# Power.net
KiCad netlist of a schematic drawn in Altium Designer
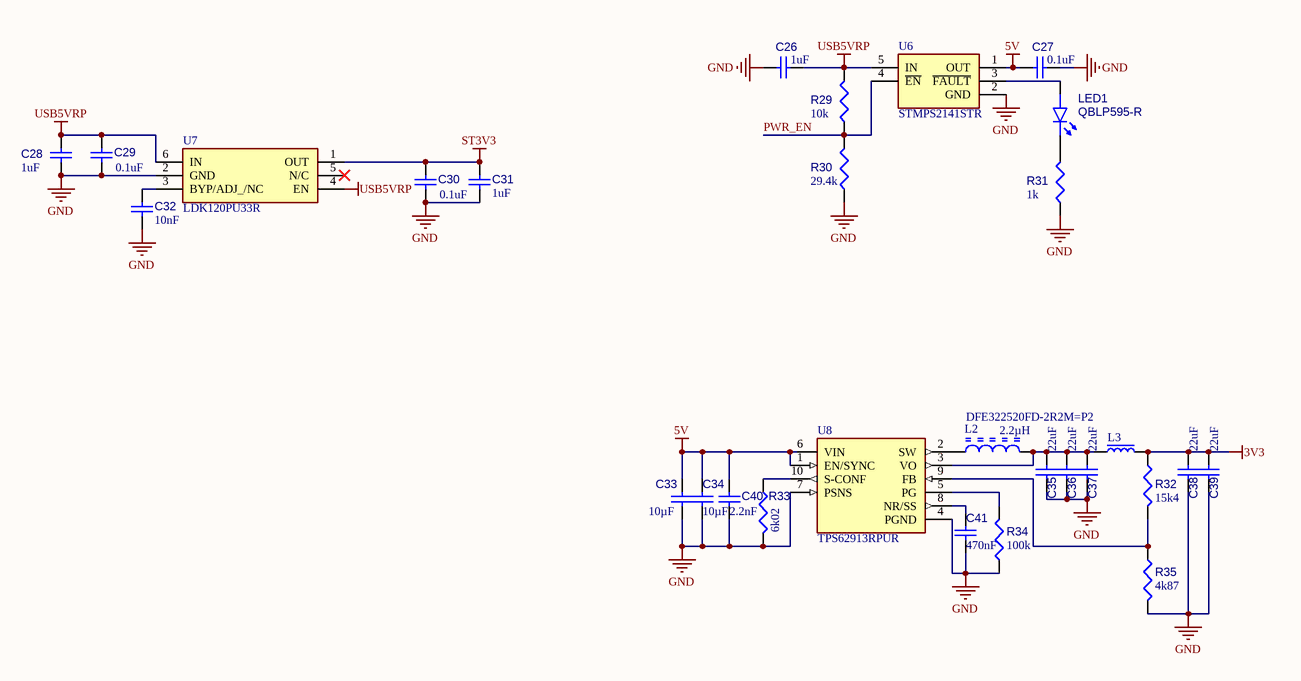
[diagram p0: Power.SchDoc]

(export (version "E")
  (design (tool "Eeschema 10.0.6"))
  (components
    (comp (ref "C26")
      (value "1uF")
      (footprint "CAPC1005X55X25ML05T05")
      (description "Chip Capacitor, 10 pF, +/- 5%, 50 V, 0402 (1005 Metric)")
      (fields (field (name "TOLERANCE") "5%") (field (name "Comment") "Capacitor 10 pF +/- 5% 50 V 0402"))
      (libsource (lib "Fei Han") (part "CAP-NP-2"))
    )
    (comp (ref "C27")
      (value "0.1uF")
      (footprint "CAPC1005X55X25ML05T05")
      (description "Chip Capacitor, 10 pF, +/- 5%, 50 V, 0402 (1005 Metric)")
      (fields (field (name "TOLERANCE") "5%") (field (name "Comment") "Capacitor 10 pF +/- 5% 50 V 0402"))
      (libsource (lib "Fei Han") (part "CAP-NP-2"))
    )
    (comp (ref "C28")
      (value "1uF")
      (footprint "CAPC1005X55X25ML05T05")
      (description "Chip Capacitor, 10 pF, +/- 5%, 50 V, 0402 (1005 Metric)")
      (fields (field (name "TOLERANCE") "5%") (field (name "Comment") "Capacitor 10 pF +/- 5% 50 V 0402"))
      (libsource (lib "Fei Han") (part "CAP-NP-2"))
    )
    (comp (ref "C29")
      (value "0.1uF")
      (footprint "CAPC1005X55X25ML05T05")
      (description "Chip Capacitor, 10 pF, +/- 5%, 50 V, 0402 (1005 Metric)")
      (fields (field (name "TOLERANCE") "5%") (field (name "Comment") "Capacitor 10 pF +/- 5% 50 V 0402"))
      (libsource (lib "Fei Han") (part "CAP-NP-2"))
    )
    (comp (ref "C30")
      (value "0.1uF")
      (footprint "CAPC1005X55X25ML05T05")
      (description "Chip Capacitor, 10 pF, +/- 5%, 50 V, 0402 (1005 Metric)")
      (fields (field (name "TOLERANCE") "5%") (field (name "Comment") "Capacitor 10 pF +/- 5% 50 V 0402"))
      (libsource (lib "Fei Han") (part "CAP-NP-2"))
    )
    (comp (ref "C31")
      (value "1uF")
      (footprint "CAPC1005X55X25ML05T05")
      (description "Chip Capacitor, 10 pF, +/- 5%, 50 V, 0402 (1005 Metric)")
      (fields (field (name "TOLERANCE") "5%") (field (name "Comment") "Capacitor 10 pF +/- 5% 50 V 0402"))
      (libsource (lib "Fei Han") (part "CAP-NP-2"))
    )
    (comp (ref "C32")
      (value "10nF")
      (footprint "CAPC1005X55X25ML05T05")
      (description "Chip Capacitor, 10 pF, +/- 5%, 50 V, 0402 (1005 Metric)")
      (fields (field (name "TOLERANCE") "5%") (field (name "Comment") "Capacitor 10 pF +/- 5% 50 V 0402"))
      (libsource (lib "Fei Han") (part "CAP-NP-2"))
    )
    (comp (ref "C33")
      (value "10µF")
      (footprint "CAPC2013X135X45NL10T25")
      (description "Chip Capacitor, 1 uF, +/- 10%, 50 V, 0805 (2012 Metric)")
      (fields (field (name "TOLERANCE") "10%") (field (name "Comment") "Capacitor 1 uF +/- 10% 50 V 0805"))
      (libsource (lib "Fei Han") (part "CAP-NP-2"))
    )
    (comp (ref "C34")
      (value "10µF")
      (footprint "CAPC2013X135X45NL10T25")
      (description "Chip Capacitor, 1 uF, +/- 10%, 50 V, 0805 (2012 Metric)")
      (fields (field (name "TOLERANCE") "10%") (field (name "Comment") "Capacitor 1 uF +/- 10% 50 V 0805"))
      (libsource (lib "Fei Han") (part "CAP-NP-2"))
    )
    (comp (ref "C35")
      (value "22uF")
      (footprint "CAPC3216X180X50ML20T25")
      (description "Chip Capacitor, 10 uF, +/- 10%, 16 V, 1206 (3216 Metric)")
      (fields (field (name "TOLERANCE") "10%") (field (name "Comment") "Capacitor 10 uF +/- 10% 16 V 1206"))
      (libsource (lib "Fei Han") (part "CAP-NP-2"))
    )
    (comp (ref "C36")
      (value "22uF")
      (footprint "CAPC3216X180X50ML20T25")
      (description "Chip Capacitor, 10 uF, +/- 10%, 16 V, 1206 (3216 Metric)")
      (fields (field (name "TOLERANCE") "10%") (field (name "Comment") "Capacitor 10 uF +/- 10% 16 V 1206"))
      (libsource (lib "Fei Han") (part "CAP-NP-2"))
    )
    (comp (ref "C37")
      (value "22uF")
      (footprint "CAPC3216X180X50ML20T25")
      (description "Chip Capacitor, 10 uF, +/- 10%, 16 V, 1206 (3216 Metric)")
      (fields (field (name "TOLERANCE") "10%") (field (name "Comment") "Capacitor 10 uF +/- 10% 16 V 1206"))
      (libsource (lib "Fei Han") (part "CAP-NP-2"))
    )
    (comp (ref "C38")
      (value "22uF")
      (footprint "CAPC3216X180X50ML20T25")
      (description "Chip Capacitor, 10 uF, +/- 10%, 16 V, 1206 (3216 Metric)")
      (fields (field (name "TOLERANCE") "10%") (field (name "Comment") "Capacitor 10 uF +/- 10% 16 V 1206"))
      (libsource (lib "Fei Han") (part "CAP-NP-2"))
    )
    (comp (ref "C39")
      (value "22uF")
      (footprint "CAPC3216X180X50ML20T25")
      (description "Chip Capacitor, 10 uF, +/- 10%, 16 V, 1206 (3216 Metric)")
      (fields (field (name "TOLERANCE") "10%") (field (name "Comment") "Capacitor 10 uF +/- 10% 16 V 1206"))
      (libsource (lib "Fei Han") (part "CAP-NP-2"))
    )
    (comp (ref "C40")
      (value "2.2nF")
      (footprint "CAPC1005X55X25ML05T05")
      (description "Chip Capacitor, 10 pF, +/- 5%, 50 V, 0402 (1005 Metric)")
      (fields (field (name "TOLERANCE") "5%") (field (name "Comment") "Capacitor 10 pF +/- 5% 50 V 0402"))
      (libsource (lib "Fei Han") (part "CAP-NP-2"))
    )
    (comp (ref "C41")
      (value "470nF")
      (footprint "CAPC1005X55X25ML05T05")
      (description "Chip Capacitor, 10 pF, +/- 5%, 50 V, 0402 (1005 Metric)")
      (fields (field (name "TOLERANCE") "5%") (field (name "Comment") "Capacitor 10 pF +/- 5% 50 V 0402"))
      (libsource (lib "Fei Han") (part "CAP-NP-2"))
    )
    (comp (ref "L2")
      (value "DFE322520FD-2R2M=P2")
      (footprint "BOUR-CM322522_V")
      (description "Chip Inductor, 2.2 uH, +/- 10%, -40 to 125 degC, 1210 (3225 Metric), RoHS, Tape and Reel")
      (fields
        (field (name "INDUCTANCE") "2.2µH")
        (field (name "MANUFACTURER") "Bourns")
        (field (name "TOLERANCE") "10%")
      )
      (libsource (lib "Fei Han") (part "BOUR-IND-2A"))
    )
    (comp (ref "L3")
      (value "FB_0603")
      (footprint "FB_0603")
      (description "Ferrite Bead SMD 0603 BLE18PS080SN1D Murata")
      (fields (field (name "SOURCE") "Schematic-Lib-PhilsLab.SchLib"))
      (libsource (lib "Fei Han") (part "FB_0805"))
    )
    (comp (ref "LED1")
      (value "QBLP595-R")
      (footprint "QTB-QBLP595_V")
      (description "Chip LED 0402, Red, 0.02 A, 2.0 to 2.5 V, -40 to 80 degC, 2-Pin SMD, RoHS, Tape and Reel")
      (libsource (lib "Fei Han") (part "LED-KA-2"))
    )
    (comp (ref "R29")
      (value "10k")
      (footprint "RESC1005X40X25ML10T10")
      (description "Chip Resistor, 15 KOhm, +/- 1%, 0.063 W, -55 to 155 degC, 0402 (1005 Metric)")
      (fields (field (name "POWER") "63mW") (field (name "TOLERANCE") "1%"))
      (libsource (lib "Fei Han") (part "RES-2"))
    )
    (comp (ref "R30")
      (value "29.4k")
      (footprint "RESC1005X40X25ML10T10")
      (description "Chip Resistor, 15 KOhm, +/- 1%, 0.063 W, -55 to 155 degC, 0402 (1005 Metric)")
      (fields (field (name "POWER") "63mW") (field (name "TOLERANCE") "1%"))
      (libsource (lib "Fei Han") (part "RES-2"))
    )
    (comp (ref "R31")
      (value "1k")
      (footprint "RESC1005X40X25ML10T10")
      (description "Chip Resistor, 15 KOhm, +/- 1%, 0.063 W, -55 to 155 degC, 0402 (1005 Metric)")
      (fields (field (name "POWER") "63mW") (field (name "TOLERANCE") "1%"))
      (libsource (lib "Fei Han") (part "RES-2"))
    )
    (comp (ref "R32")
      (value "15k4")
      (footprint "RESC1005X40X25ML10T10")
      (description "Chip Resistor, 15 KOhm, +/- 1%, 0.063 W, -55 to 155 degC, 0402 (1005 Metric)")
      (fields (field (name "POWER") "63mW") (field (name "TOLERANCE") "1%"))
      (libsource (lib "Fei Han") (part "RES-2"))
    )
    (comp (ref "R33")
      (value "6k02")
      (footprint "RESC1005X40X25ML10T10")
      (description "Chip Resistor, 15 KOhm, +/- 1%, 0.063 W, -55 to 155 degC, 0402 (1005 Metric)")
      (fields (field (name "POWER") "63mW") (field (name "TOLERANCE") "1%"))
      (libsource (lib "Fei Han") (part "RES-2"))
    )
    (comp (ref "R34")
      (value "100k")
      (footprint "RESC1005X40X25ML10T10")
      (description "Chip Resistor, 15 KOhm, +/- 1%, 0.063 W, -55 to 155 degC, 0402 (1005 Metric)")
      (fields (field (name "POWER") "63mW") (field (name "TOLERANCE") "1%"))
      (libsource (lib "Fei Han") (part "RES-2"))
    )
    (comp (ref "R35")
      (value "4k87")
      (footprint "RESC1005X40X25ML10T10")
      (description "Chip Resistor, 15 KOhm, +/- 1%, 0.063 W, -55 to 155 degC, 0402 (1005 Metric)")
      (fields (field (name "POWER") "63mW") (field (name "TOLERANCE") "1%"))
      (libsource (lib "Fei Han") (part "RES-2"))
    )
    (comp (ref "U6")
      (value "STMPS2141STR")
      (footprint "FP-SOT23-5L-IPC_C")
      (description "Buffer/Inverter Based Peripheral Driver, 1 Driver, PDSO5")
      (libsource (lib "Fei Han") (part "dcdbc575d070b0201d64222148af8d2"))
    )
    (comp (ref "U7")
      (value "LDK120PU33R")
      (footprint "LDK120PU33R")
      (description "STMicroelectronics LDK120PU33R, LDO Voltage Regulator, 200mA, 3.3 V +/-3%, 1.9  5.5 Vin, 6-Pin DFN")
      (fields (field (name "MOUSER PART NUMBER") "511-LDK120PU33R"))
      (libsource (lib "Fei Han") (part "LDK120PU33R"))
    )
    (comp (ref "U8")
      (value "TPS62913RPUR")
      (footprint "FP-RPU0010A-MFG")
      (description "Switching Regulator, Current-mode, 2A, 2420kHz Switching Freq-Max")
      (libsource (lib "Fei Han") (part "fcf13f863b056b866477b745cbfb11f"))
    )
  )
  (nets
    (net (code "1") (name "/PWR_EN") (class "Default")
      (node (ref "R29") (pin "1") (pinfunction "1_1") (pintype "passive"))
      (node (ref "R30") (pin "2") (pinfunction "2_2") (pintype "passive"))
      (node (ref "U6") (pin "4") (pinfunction "~{EN}_4") (pintype "passive"))
    )
    (net (code "2") (name "3V3") (class "Default")
      (node (ref "C38") (pin "2") (pinfunction "2_2") (pintype "passive"))
      (node (ref "C39") (pin "2") (pinfunction "2_2") (pintype "passive"))
      (node (ref "L3") (pin "2") (pinfunction "2_2") (pintype "passive"))
      (node (ref "R32") (pin "1") (pinfunction "1_1") (pintype "passive"))
    )
    (net (code "3") (name "5V") (class "Default")
      (node (ref "C27") (pin "1") (pinfunction "1_1") (pintype "passive"))
      (node (ref "C33") (pin "2") (pinfunction "2_2") (pintype "passive"))
      (node (ref "C34") (pin "2") (pinfunction "2_2") (pintype "passive"))
      (node (ref "C40") (pin "2") (pinfunction "2_2") (pintype "passive"))
      (node (ref "U6") (pin "1") (pinfunction "OUT_1") (pintype "passive"))
      (node (ref "U8") (pin "1") (pinfunction "EN/SYNC_1") (pintype "input"))
      (node (ref "U8") (pin "6") (pinfunction "VIN_6") (pintype "power_in"))
    )
    (net (code "4") (name "GND") (class "Default")
      (node (ref "C26") (pin "1") (pinfunction "1_1") (pintype "passive"))
      (node (ref "C27") (pin "2") (pinfunction "2_2") (pintype "passive"))
      (node (ref "C28") (pin "1") (pinfunction "1_1") (pintype "passive"))
      (node (ref "C29") (pin "1") (pinfunction "1_1") (pintype "passive"))
      (node (ref "C30") (pin "1") (pinfunction "1_1") (pintype "passive"))
      (node (ref "C31") (pin "2") (pinfunction "2_2") (pintype "passive"))
      (node (ref "C32") (pin "1") (pinfunction "1_1") (pintype "passive"))
      (node (ref "C33") (pin "1") (pinfunction "1_1") (pintype "passive"))
      (node (ref "C34") (pin "1") (pinfunction "1_1") (pintype "passive"))
      (node (ref "C35") (pin "1") (pinfunction "1_1") (pintype "passive"))
      (node (ref "C36") (pin "1") (pinfunction "1_1") (pintype "passive"))
      (node (ref "C37") (pin "1") (pinfunction "1_1") (pintype "passive"))
      (node (ref "C38") (pin "1") (pinfunction "1_1") (pintype "passive"))
      (node (ref "C39") (pin "1") (pinfunction "1_1") (pintype "passive"))
      (node (ref "C40") (pin "1") (pinfunction "1_1") (pintype "passive"))
      (node (ref "C41") (pin "1") (pinfunction "1_1") (pintype "passive"))
      (node (ref "R30") (pin "1") (pinfunction "1_1") (pintype "passive"))
      (node (ref "R31") (pin "1") (pinfunction "1_1") (pintype "passive"))
      (node (ref "R33") (pin "2") (pinfunction "2_2") (pintype "passive"))
      (node (ref "R34") (pin "2") (pinfunction "2_2") (pintype "passive"))
      (node (ref "R35") (pin "2") (pinfunction "2_2") (pintype "passive"))
      (node (ref "U6") (pin "2") (pinfunction "GND_2") (pintype "passive"))
      (node (ref "U7") (pin "2") (pinfunction "GND_2") (pintype "passive"))
      (node (ref "U8") (pin "4") (pinfunction "PGND_4") (pintype "passive"))
      (node (ref "U8") (pin "7") (pinfunction "PSNS_7") (pintype "input"))
    )
    (net (code "5") (name "Net-(LED1-A)") (class "Default")
      (node (ref "LED1") (pin "2") (pinfunction "A_2") (pintype "passive"))
      (node (ref "U6") (pin "3") (pinfunction "~{FAULT}_3") (pintype "open_collector"))
    )
    (net (code "6") (name "Net-(LED1-K)") (class "Default")
      (node (ref "LED1") (pin "1") (pinfunction "K_1") (pintype "passive"))
      (node (ref "R31") (pin "2") (pinfunction "2_2") (pintype "passive"))
    )
    (net (code "7") (name "Net-(U7-BYP{slash}ADJ_{slash}NC)") (class "Default")
      (node (ref "C32") (pin "2") (pinfunction "2_2") (pintype "passive"))
      (node (ref "U7") (pin "3") (pinfunction "BYP/ADJ_/NC_3") (pintype "passive"))
    )
    (net (code "8") (name "Net-(U8-FB)") (class "Default")
      (node (ref "R32") (pin "2") (pinfunction "2_2") (pintype "passive"))
      (node (ref "R35") (pin "1") (pinfunction "1_1") (pintype "passive"))
      (node (ref "U8") (pin "9") (pinfunction "FB_9") (pintype "input"))
    )
    (net (code "9") (name "Net-(U8-NR{slash}SS)") (class "Default")
      (node (ref "C41") (pin "2") (pinfunction "2_2") (pintype "passive"))
      (node (ref "U8") (pin "8") (pinfunction "NR/SS_8") (pintype "output"))
    )
    (net (code "10") (name "Net-(U8-PG)") (class "Default")
      (node (ref "R34") (pin "1") (pinfunction "1_1") (pintype "passive"))
      (node (ref "U8") (pin "5") (pinfunction "PG_5") (pintype "open_collector"))
    )
    (net (code "11") (name "Net-(U8-S-CONF)") (class "Default")
      (node (ref "R33") (pin "1") (pinfunction "1_1") (pintype "passive"))
      (node (ref "U8") (pin "10") (pinfunction "S-CONF_10") (pintype "output"))
    )
    (net (code "12") (name "Net-(U8-SW)") (class "Default")
      (node (ref "L2") (pin "1") (pinfunction "1_1") (pintype "passive"))
      (node (ref "U8") (pin "2") (pinfunction "SW_2") (pintype "output"))
    )
    (net (code "13") (name "Net-(U8-VO)") (class "Default")
      (node (ref "C35") (pin "2") (pinfunction "2_2") (pintype "passive"))
      (node (ref "C36") (pin "2") (pinfunction "2_2") (pintype "passive"))
      (node (ref "C37") (pin "2") (pinfunction "2_2") (pintype "passive"))
      (node (ref "L2") (pin "2") (pinfunction "2_2") (pintype "passive"))
      (node (ref "L3") (pin "1") (pinfunction "1_1") (pintype "passive"))
      (node (ref "U8") (pin "3") (pinfunction "VO_3") (pintype "output"))
    )
    (net (code "14") (name "ST3V3") (class "Default")
      (node (ref "C30") (pin "2") (pinfunction "2_2") (pintype "passive"))
      (node (ref "C31") (pin "1") (pinfunction "1_1") (pintype "passive"))
      (node (ref "U7") (pin "1") (pinfunction "OUT_1") (pintype "passive"))
    )
    (net (code "15") (name "USB5VRP") (class "Default")
      (node (ref "C26") (pin "2") (pinfunction "2_2") (pintype "passive"))
      (node (ref "C28") (pin "2") (pinfunction "2_2") (pintype "passive"))
      (node (ref "C29") (pin "2") (pinfunction "2_2") (pintype "passive"))
      (node (ref "R29") (pin "2") (pinfunction "2_2") (pintype "passive"))
      (node (ref "U6") (pin "5") (pinfunction "IN_5") (pintype "passive"))
      (node (ref "U7") (pin "4") (pinfunction "EN_4") (pintype "passive"))
      (node (ref "U7") (pin "6") (pinfunction "IN_6") (pintype "passive"))
    )
    (net (code "16") (name "unconnected-(U7-N{slash}C-Pad5)") (class "Default")
      (node (ref "U7") (pin "5") (pinfunction "N/C_5") (pintype "passive+no_connect"))
    )
  )
)
